# DMP_SEM_MCU.net
KiCad netlist of a schematic drawn in Altium Designer
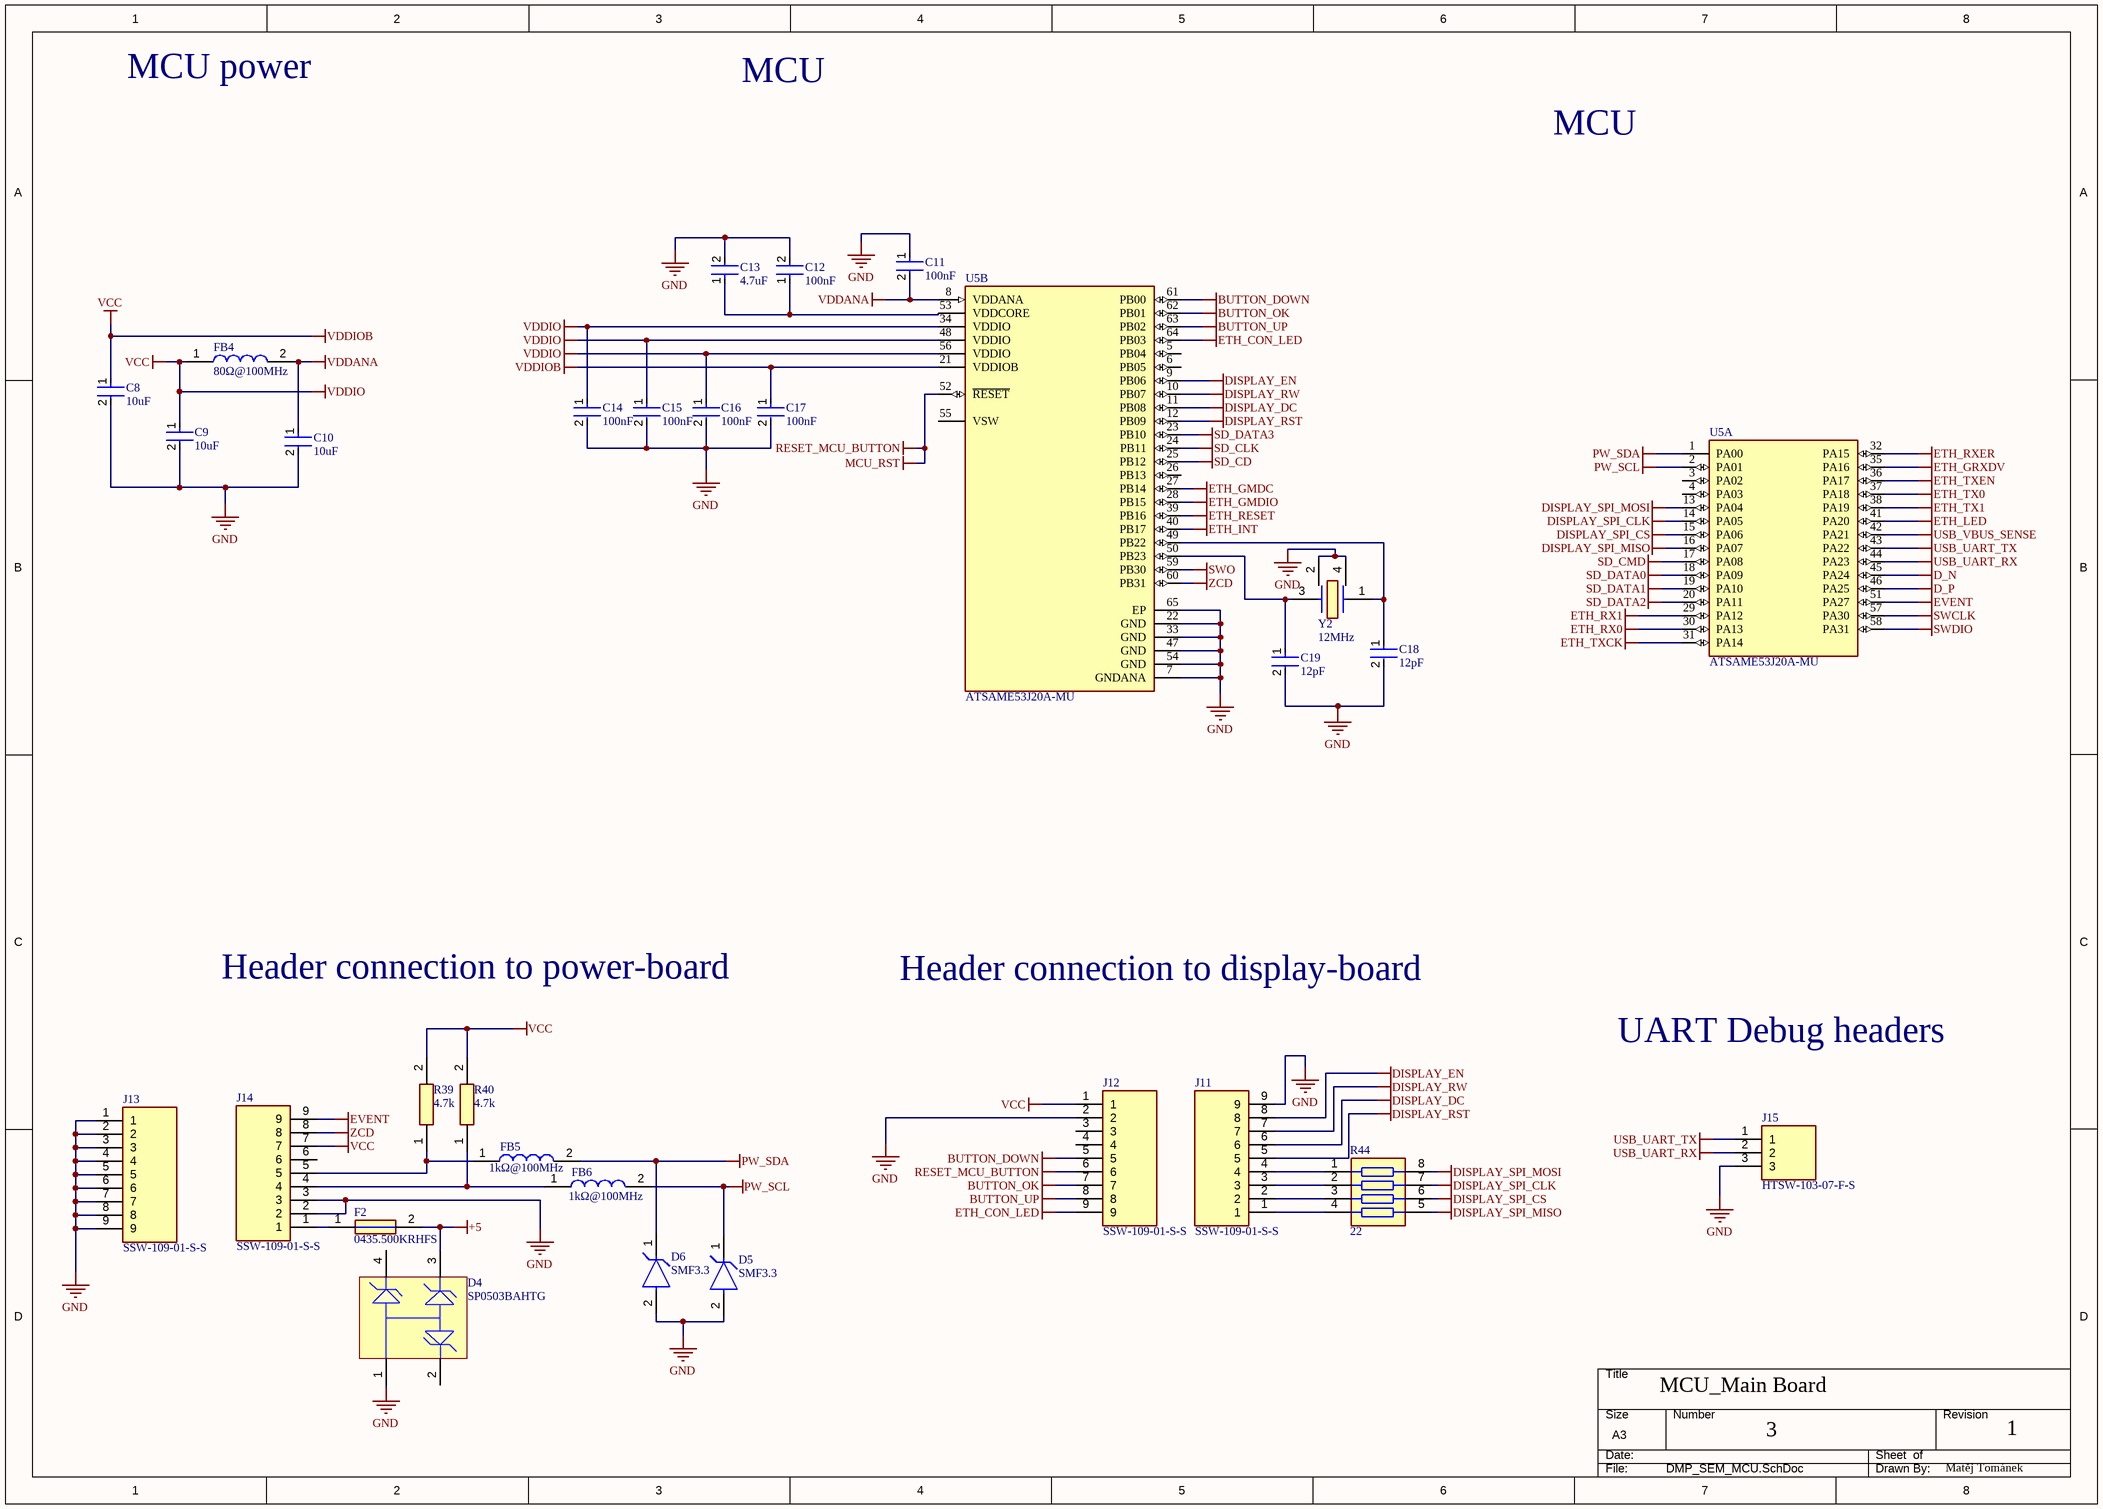
[diagram p0: DMP_SEM_MCU.SchDoc]

(export (version "E")
  (design (tool "Eeschema 10.0.6"))
  (components
    (comp (ref "C8")
      (value "10uF")
      (footprint "CL10A106KO8NQNC")
      (description "Capacitor CL10A106KO8NQNC")
      (libsource (lib "DMP_Schlib_SEM_MAIN_BOARD") (part "CL10A106KO8NQNC"))
    )
    (comp (ref "C9")
      (value "10uF")
      (footprint "CL10A106KO8NQNC")
      (description "Capacitor CL10A106KO8NQNC")
      (libsource (lib "DMP_Schlib_SEM_MAIN_BOARD") (part "CL10A106KO8NQNC"))
    )
    (comp (ref "C10")
      (value "10uF")
      (footprint "CL10A106KO8NQNC")
      (description "Capacitor CL10A106KO8NQNC")
      (libsource (lib "DMP_Schlib_SEM_MAIN_BOARD") (part "CL10A106KO8NQNC"))
    )
    (comp (ref "C11")
      (value "100nF")
      (footprint "CL05B104KO5NNNC")
      (description "Capacitor CL05B104KO5NNNC")
      (libsource (lib "DMP_Schlib_SEM_MAIN_BOARD") (part "CL05B104KO5NNNC"))
    )
    (comp (ref "C12")
      (value "100nF")
      (footprint "CL05B104KO5NNNC")
      (description "Capacitor CL05B104KO5NNNC")
      (libsource (lib "DMP_Schlib_SEM_MAIN_BOARD") (part "CL05B104KO5NNNC"))
    )
    (comp (ref "C13")
      (value "4.7uF")
      (footprint "CL05A475KP5NRNC")
      (description "Capacitor CL05A475KP5NRNC")
      (libsource (lib "DMP_Schlib_SEM_MAIN_BOARD") (part "CL05A475KP5NRNC"))
    )
    (comp (ref "C14")
      (value "100nF")
      (footprint "CL05B104KO5NNNC")
      (description "Capacitor CL05B104KO5NNNC")
      (libsource (lib "DMP_Schlib_SEM_MAIN_BOARD") (part "CL05B104KO5NNNC"))
    )
    (comp (ref "C15")
      (value "100nF")
      (footprint "CL05B104KO5NNNC")
      (description "Capacitor CL05B104KO5NNNC")
      (libsource (lib "DMP_Schlib_SEM_MAIN_BOARD") (part "CL05B104KO5NNNC"))
    )
    (comp (ref "C16")
      (value "100nF")
      (footprint "CL05B104KO5NNNC")
      (description "Capacitor CL05B104KO5NNNC")
      (libsource (lib "DMP_Schlib_SEM_MAIN_BOARD") (part "CL05B104KO5NNNC"))
    )
    (comp (ref "C17")
      (value "100nF")
      (footprint "CL05B104KO5NNNC")
      (description "Capacitor CL05B104KO5NNNC")
      (libsource (lib "DMP_Schlib_SEM_MAIN_BOARD") (part "CL05B104KO5NNNC"))
    )
    (comp (ref "C18")
      (value "12pF")
      (footprint "GRM1555C1H120JA01D")
      (description "Capacitor GRM1555C1H120JA01D")
      (libsource (lib "DMP_Schlib_SEM_MAIN_BOARD") (part "GRM1555C1H120JA01D"))
    )
    (comp (ref "C19")
      (value "12pF")
      (footprint "GRM1555C1H120JA01D")
      (description "Capacitor GRM1555C1H120JA01D")
      (libsource (lib "DMP_Schlib_SEM_MAIN_BOARD") (part "GRM1555C1H120JA01D"))
    )
    (comp (ref "D4")
      (value "SP0503BAHTG")
      (footprint "SP0503BAHTG")
      (description "TVS Diodes SP0503BAHTG")
      (libsource (lib "DMP_Schlib_SEM_MAIN_BOARD") (part "SP0503BAHTG"))
    )
    (comp (ref "D5")
      (value "SMF3.3")
      (footprint "SMF3.3")
      (description "TVS diode SMF3.3")
      (libsource (lib "DMP_Schlib_SEM_MAIN_BOARD") (part "SMF3.3"))
    )
    (comp (ref "D6")
      (value "SMF3.3")
      (footprint "SMF3.3")
      (description "TVS diode SMF3.3")
      (libsource (lib "DMP_Schlib_SEM_MAIN_BOARD") (part "SMF3.3"))
    )
    (comp (ref "F2")
      (value "0435.500KRHFS")
      (footprint "0435.500KRHFS")
      (description "Fuse 0435.500KRHFS")
      (libsource (lib "DMP_Schlib_SEM_MAIN_BOARD") (part "0435.500KRHFS"))
    )
    (comp (ref "FB4")
      (value "80Ω@100MHz")
      (footprint "BLM15PD800SN1D")
      (description "Chip Ferrite Bead BLM15PD800SN1D")
      (libsource (lib "DMP_Schlib_SEM_MAIN_BOARD") (part "BLM15PD800SN1D"))
    )
    (comp (ref "FB5")
      (value "1kΩ@100MHz")
      (footprint "BLM15BD102SN1D")
      (description "Chip Ferrite Bead BLM15BD102SN1D")
      (libsource (lib "DMP_Schlib_SEM_MAIN_BOARD") (part "BLM15BD102SN1D"))
    )
    (comp (ref "FB6")
      (value "1kΩ@100MHz")
      (footprint "BLM15BD102SN1D")
      (description "Chip Ferrite Bead BLM15BD102SN1D")
      (libsource (lib "DMP_Schlib_SEM_MAIN_BOARD") (part "BLM15BD102SN1D"))
    )
    (comp (ref "J11")
      (value "SSW-109-01-S-S")
      (footprint "SSW-109-01-S-S")
      (description "Connector SSW-109-01-S-S")
      (libsource (lib "DMP_Schlib_SEM_MAIN_BOARD") (part "SSW-109-01-S-S"))
    )
    (comp (ref "J12")
      (value "SSW-109-01-S-S")
      (footprint "SSW-109-01-S-S")
      (description "Connector SSW-109-01-S-S")
      (libsource (lib "") (part "SSW-109-01-S-S_1"))
    )
    (comp (ref "J13")
      (value "SSW-109-01-S-S")
      (footprint "SSW-109-01-S-S")
      (description "Connector SSW-109-01-S-S")
      (libsource (lib "") (part "SSW-109-01-S-S_1"))
    )
    (comp (ref "J14")
      (value "SSW-109-01-S-S")
      (footprint "SSW-109-01-S-S")
      (description "Connector SSW-109-01-S-S")
      (libsource (lib "DMP_Schlib_SEM_MAIN_BOARD") (part "SSW-109-01-S-S"))
    )
    (comp (ref "J15")
      (value "HTSW-103-07-F-S")
      (footprint "HTSW-103-07-F-S")
      (description "Headers HTSW-103-07-F-S")
      (libsource (lib "DMP_Schlib_SEM_MAIN_BOARD") (part "HTSW-103-07-F-S"))
    )
    (comp (ref "R39")
      (value "4.7k")
      (footprint "ERJ-3EKF4701V")
      (description "Resistor ERJ-3EKF4701V")
      (libsource (lib "DMP_Schlib_SEM_MAIN_BOARD") (part "ERJ-3EKF4701V"))
    )
    (comp (ref "R40")
      (value "4.7k")
      (footprint "ERJ-3EKF4701V")
      (description "Resistor ERJ-3EKF4701V")
      (libsource (lib "DMP_Schlib_SEM_MAIN_BOARD") (part "ERJ-3EKF4701V"))
    )
    (comp (ref "R44")
      (value "22")
      (footprint "CAY10-220J4LF")
      (description "Resistor array CAY10-220J4LF")
      (libsource (lib "DMP_Schlib_SEM_MAIN_BOARD") (part "CAY10-220J4LF"))
    )
    (comp (ref "U5")
      (value "ATSAME53J20A-MU")
      (footprint "FP-PA-IPC_A")
      (description "IC MCU 32BIT 1MB FLASH 64VQFN")
      (libsource (lib "Altium Content Vault") (part "236593db3e601640e0235ea4da59ade"))
    )
    (comp (ref "Y2")
      (value "12MHz")
      (footprint "ABM8W-12.0000MHZ-6-B1U-T3")
      (description "Crystal ABM8W-12.0000MHZ-6-B1U-T3")
      (libsource (lib "DMP_Schlib_SEM_MAIN_BOARD") (part "ABM8W-12.0000MHZ-6-B1U-T3"))
    )
  )
  (nets
    (net (code "1") (name "+5") (class "Default")
      (node (ref "D4") (pin "3") (pinfunction "3_3") (pintype "passive"))
      (node (ref "F2") (pin "2") (pinfunction "2_2") (pintype "passive"))
    )
    (net (code "2") (name "BUTTON_DOWN") (class "Default")
      (node (ref "J12") (pin "5") (pinfunction "5_5") (pintype "passive"))
      (node (ref "U5") (pin "61") (pinfunction "PB00_61") (pintype "bidirectional"))
    )
    (net (code "3") (name "BUTTON_OK") (class "Default")
      (node (ref "J12") (pin "7") (pinfunction "7_7") (pintype "passive"))
      (node (ref "U5") (pin "62") (pinfunction "PB01_62") (pintype "bidirectional"))
    )
    (net (code "4") (name "BUTTON_UP") (class "Default")
      (node (ref "J12") (pin "8") (pinfunction "8_8") (pintype "passive"))
      (node (ref "U5") (pin "63") (pinfunction "PB02_63") (pintype "bidirectional"))
    )
    (net (code "5") (name "DISPLAY_DC") (class "Default")
      (node (ref "J11") (pin "6") (pinfunction "6_6") (pintype "passive"))
      (node (ref "U5") (pin "11") (pinfunction "PB08_11") (pintype "bidirectional"))
    )
    (net (code "6") (name "DISPLAY_EN") (class "Default")
      (node (ref "J11") (pin "8") (pinfunction "8_8") (pintype "passive"))
      (node (ref "U5") (pin "9") (pinfunction "PB06_9") (pintype "bidirectional"))
    )
    (net (code "7") (name "DISPLAY_RST") (class "Default")
      (node (ref "J11") (pin "5") (pinfunction "5_5") (pintype "passive"))
      (node (ref "U5") (pin "12") (pinfunction "PB09_12") (pintype "bidirectional"))
    )
    (net (code "8") (name "DISPLAY_RW") (class "Default")
      (node (ref "J11") (pin "7") (pinfunction "7_7") (pintype "passive"))
      (node (ref "U5") (pin "10") (pinfunction "PB07_10") (pintype "bidirectional"))
    )
    (net (code "9") (name "DISPLAY_SPI_CLK") (class "Default")
      (node (ref "R44") (pin "7") (pintype "passive"))
      (node (ref "U5") (pin "14") (pinfunction "PA05_14") (pintype "bidirectional"))
    )
    (net (code "10") (name "DISPLAY_SPI_CS") (class "Default")
      (node (ref "R44") (pin "6") (pintype "passive"))
      (node (ref "U5") (pin "15") (pinfunction "PA06_15") (pintype "bidirectional"))
    )
    (net (code "11") (name "DISPLAY_SPI_MISO") (class "Default")
      (node (ref "R44") (pin "5") (pintype "passive"))
      (node (ref "U5") (pin "16") (pinfunction "PA07_16") (pintype "bidirectional"))
    )
    (net (code "12") (name "DISPLAY_SPI_MOSI") (class "Default")
      (node (ref "R44") (pin "8") (pintype "passive"))
      (node (ref "U5") (pin "13") (pinfunction "PA04_13") (pintype "bidirectional"))
    )
    (net (code "13") (name "D_N") (class "Default")
      (node (ref "U5") (pin "45") (pinfunction "PA24_45") (pintype "bidirectional"))
    )
    (net (code "14") (name "D_P") (class "Default")
      (node (ref "U5") (pin "46") (pinfunction "PA25_46") (pintype "bidirectional"))
    )
    (net (code "15") (name "ETH_CON_LED") (class "Default")
      (node (ref "J12") (pin "9") (pinfunction "9_9") (pintype "passive"))
      (node (ref "U5") (pin "64") (pinfunction "PB03_64") (pintype "bidirectional"))
    )
    (net (code "16") (name "ETH_GMDC") (class "Default")
      (node (ref "U5") (pin "27") (pinfunction "PB14_27") (pintype "bidirectional"))
    )
    (net (code "17") (name "ETH_GMDIO") (class "Default")
      (node (ref "U5") (pin "28") (pinfunction "PB15_28") (pintype "bidirectional"))
    )
    (net (code "18") (name "ETH_GRXDV") (class "Default")
      (node (ref "U5") (pin "35") (pinfunction "PA16_35") (pintype "bidirectional"))
    )
    (net (code "19") (name "ETH_INT") (class "Default")
      (node (ref "U5") (pin "40") (pinfunction "PB17_40") (pintype "bidirectional"))
    )
    (net (code "20") (name "ETH_LED") (class "Default")
      (node (ref "U5") (pin "41") (pinfunction "PA20_41") (pintype "bidirectional"))
    )
    (net (code "21") (name "ETH_RESET") (class "Default")
      (node (ref "U5") (pin "39") (pinfunction "PB16_39") (pintype "bidirectional"))
    )
    (net (code "22") (name "ETH_RX0") (class "Default")
      (node (ref "U5") (pin "30") (pinfunction "PA13_30") (pintype "bidirectional"))
    )
    (net (code "23") (name "ETH_RX1") (class "Default")
      (node (ref "U5") (pin "29") (pinfunction "PA12_29") (pintype "bidirectional"))
    )
    (net (code "24") (name "ETH_RXER") (class "Default")
      (node (ref "U5") (pin "32") (pinfunction "PA15_32") (pintype "bidirectional"))
    )
    (net (code "25") (name "ETH_TX0") (class "Default")
      (node (ref "U5") (pin "37") (pinfunction "PA18_37") (pintype "bidirectional"))
    )
    (net (code "26") (name "ETH_TX1") (class "Default")
      (node (ref "U5") (pin "38") (pinfunction "PA19_38") (pintype "bidirectional"))
    )
    (net (code "27") (name "ETH_TXCK") (class "Default")
      (node (ref "U5") (pin "31") (pinfunction "PA14_31") (pintype "bidirectional"))
    )
    (net (code "28") (name "ETH_TXEN") (class "Default")
      (node (ref "U5") (pin "36") (pinfunction "PA17_36") (pintype "bidirectional"))
    )
    (net (code "29") (name "EVENT") (class "Default")
      (node (ref "J14") (pin "9") (pinfunction "9_9") (pintype "passive"))
      (node (ref "U5") (pin "51") (pinfunction "PA27_51") (pintype "bidirectional"))
    )
    (net (code "30") (name "GND") (class "Default")
      (node (ref "C10") (pin "2") (pinfunction "2_2") (pintype "passive"))
      (node (ref "C11") (pin "1") (pinfunction "1_1") (pintype "passive"))
      (node (ref "C12") (pin "2") (pinfunction "2_2") (pintype "passive"))
      (node (ref "C13") (pin "2") (pinfunction "2_2") (pintype "passive"))
      (node (ref "C14") (pin "2") (pinfunction "2_2") (pintype "passive"))
      (node (ref "C15") (pin "2") (pinfunction "2_2") (pintype "passive"))
      (node (ref "C16") (pin "2") (pinfunction "2_2") (pintype "passive"))
      (node (ref "C17") (pin "2") (pinfunction "2_2") (pintype "passive"))
      (node (ref "C18") (pin "2") (pinfunction "2_2") (pintype "passive"))
      (node (ref "C19") (pin "2") (pinfunction "2_2") (pintype "passive"))
      (node (ref "C8") (pin "2") (pinfunction "2_2") (pintype "passive"))
      (node (ref "C9") (pin "2") (pinfunction "2_2") (pintype "passive"))
      (node (ref "D4") (pin "1") (pinfunction "1_1") (pintype "passive"))
      (node (ref "D5") (pin "2") (pinfunction "A_2") (pintype "passive"))
      (node (ref "D6") (pin "2") (pinfunction "A_2") (pintype "passive"))
      (node (ref "J11") (pin "9") (pinfunction "9_9") (pintype "passive"))
      (node (ref "J12") (pin "2") (pinfunction "2_2") (pintype "passive"))
      (node (ref "J13") (pin "1") (pinfunction "1_1") (pintype "passive"))
      (node (ref "J13") (pin "2") (pinfunction "2_2") (pintype "passive"))
      (node (ref "J13") (pin "3") (pinfunction "3_3") (pintype "passive"))
      (node (ref "J13") (pin "4") (pinfunction "4_4") (pintype "passive"))
      (node (ref "J13") (pin "5") (pinfunction "5_5") (pintype "passive"))
      (node (ref "J13") (pin "6") (pinfunction "6_6") (pintype "passive"))
      (node (ref "J13") (pin "7") (pinfunction "7_7") (pintype "passive"))
      (node (ref "J13") (pin "8") (pinfunction "8_8") (pintype "passive"))
      (node (ref "J13") (pin "9") (pinfunction "9_9") (pintype "passive"))
      (node (ref "J14") (pin "2") (pinfunction "2_2") (pintype "passive"))
      (node (ref "J14") (pin "3") (pinfunction "3_3") (pintype "passive"))
      (node (ref "J15") (pin "3") (pinfunction "3_3") (pintype "passive"))
      (node (ref "U5") (pin "22") (pinfunction "GND_22") (pintype "power_in"))
      (node (ref "U5") (pin "33") (pinfunction "GND_33") (pintype "power_in"))
      (node (ref "U5") (pin "47") (pinfunction "GND_47") (pintype "power_in"))
      (node (ref "U5") (pin "54") (pinfunction "GND_54") (pintype "power_in"))
      (node (ref "U5") (pin "65") (pinfunction "EP_65") (pintype "power_in"))
      (node (ref "U5") (pin "7") (pinfunction "GNDANA_7") (pintype "power_in"))
      (node (ref "Y2") (pin "2") (pintype "passive"))
      (node (ref "Y2") (pin "4") (pintype "passive"))
    )
    (net (code "31") (name "MCU_RST") (class "Default")
      (node (ref "J12") (pin "6") (pinfunction "6_6") (pintype "passive"))
      (node (ref "U5") (pin "52") (pinfunction "~{RESET}_52") (pintype "bidirectional"))
    )
    (net (code "32") (name "Net-(F2-Pad1)") (class "Default")
      (node (ref "F2") (pin "1") (pinfunction "1_1") (pintype "passive"))
      (node (ref "J14") (pin "1") (pinfunction "1_1") (pintype "passive"))
    )
    (net (code "33") (name "Net-(FB5-Pad1)") (class "Default")
      (node (ref "FB5") (pin "1") (pinfunction "1_1") (pintype "passive"))
      (node (ref "J14") (pin "5") (pinfunction "5_5") (pintype "passive"))
      (node (ref "R39") (pin "1") (pinfunction "1_1") (pintype "passive"))
    )
    (net (code "34") (name "Net-(FB6-Pad1)") (class "Default")
      (node (ref "FB6") (pin "1") (pinfunction "1_1") (pintype "passive"))
      (node (ref "J14") (pin "4") (pinfunction "4_4") (pintype "passive"))
      (node (ref "R40") (pin "1") (pinfunction "1_1") (pintype "passive"))
    )
    (net (code "35") (name "Net-(J11-Pad1)") (class "Default")
      (node (ref "J11") (pin "1") (pinfunction "1_1") (pintype "passive"))
      (node (ref "R44") (pin "4") (pintype "passive"))
    )
    (net (code "36") (name "Net-(J11-Pad2)") (class "Default")
      (node (ref "J11") (pin "2") (pinfunction "2_2") (pintype "passive"))
      (node (ref "R44") (pin "3") (pintype "passive"))
    )
    (net (code "37") (name "Net-(J11-Pad3)") (class "Default")
      (node (ref "J11") (pin "3") (pinfunction "3_3") (pintype "passive"))
      (node (ref "R44") (pin "2") (pintype "passive"))
    )
    (net (code "38") (name "Net-(J11-Pad4)") (class "Default")
      (node (ref "J11") (pin "4") (pinfunction "4_4") (pintype "passive"))
      (node (ref "R44") (pin "1") (pintype "passive"))
    )
    (net (code "39") (name "Net-(U5B-PB22)") (class "Default")
      (node (ref "C18") (pin "1") (pinfunction "1_1") (pintype "passive"))
      (node (ref "U5") (pin "49") (pinfunction "PB22_49") (pintype "bidirectional"))
      (node (ref "Y2") (pin "1") (pintype "passive"))
    )
    (net (code "40") (name "Net-(U5B-PB23)") (class "Default")
      (node (ref "C19") (pin "1") (pinfunction "1_1") (pintype "passive"))
      (node (ref "U5") (pin "50") (pinfunction "PB23_50") (pintype "bidirectional"))
      (node (ref "Y2") (pin "3") (pintype "passive"))
    )
    (net (code "41") (name "Net-(U5B-VDDCORE)") (class "Default")
      (node (ref "C12") (pin "1") (pinfunction "1_1") (pintype "passive"))
      (node (ref "C13") (pin "1") (pinfunction "1_1") (pintype "passive"))
      (node (ref "U5") (pin "53") (pinfunction "VDDCORE_53") (pintype "power_in"))
    )
    (net (code "42") (name "PW_SCL") (class "Default")
      (node (ref "D5") (pin "1") (pinfunction "C_1") (pintype "passive"))
      (node (ref "FB6") (pin "2") (pinfunction "2_2") (pintype "passive"))
      (node (ref "U5") (pin "2") (pinfunction "PA01_2") (pintype "bidirectional"))
    )
    (net (code "43") (name "PW_SDA") (class "Default")
      (node (ref "D6") (pin "1") (pinfunction "C_1") (pintype "passive"))
      (node (ref "FB5") (pin "2") (pinfunction "2_2") (pintype "passive"))
      (node (ref "U5") (pin "1") (pinfunction "PA00_1") (pintype "power_in"))
    )
    (net (code "44") (name "SD_CD") (class "Default")
      (node (ref "U5") (pin "25") (pinfunction "PB12_25") (pintype "bidirectional"))
    )
    (net (code "45") (name "SD_CLK") (class "Default")
      (node (ref "U5") (pin "24") (pinfunction "PB11_24") (pintype "bidirectional"))
    )
    (net (code "46") (name "SD_CMD") (class "Default")
      (node (ref "U5") (pin "17") (pinfunction "PA08_17") (pintype "bidirectional"))
    )
    (net (code "47") (name "SD_DATA0") (class "Default")
      (node (ref "U5") (pin "18") (pinfunction "PA09_18") (pintype "bidirectional"))
    )
    (net (code "48") (name "SD_DATA1") (class "Default")
      (node (ref "U5") (pin "19") (pinfunction "PA10_19") (pintype "bidirectional"))
    )
    (net (code "49") (name "SD_DATA2") (class "Default")
      (node (ref "U5") (pin "20") (pinfunction "PA11_20") (pintype "bidirectional"))
    )
    (net (code "50") (name "SD_DATA3") (class "Default")
      (node (ref "U5") (pin "23") (pinfunction "PB10_23") (pintype "bidirectional"))
    )
    (net (code "51") (name "SWCLK") (class "Default")
      (node (ref "U5") (pin "57") (pinfunction "PA30_57") (pintype "bidirectional"))
    )
    (net (code "52") (name "SWDIO") (class "Default")
      (node (ref "U5") (pin "58") (pinfunction "PA31_58") (pintype "bidirectional"))
    )
    (net (code "53") (name "SWO") (class "Default")
      (node (ref "U5") (pin "59") (pinfunction "PB30_59") (pintype "bidirectional"))
    )
    (net (code "54") (name "USB_UART_RX") (class "Default")
      (node (ref "J15") (pin "2") (pinfunction "2_2") (pintype "passive"))
      (node (ref "U5") (pin "44") (pinfunction "PA23_44") (pintype "bidirectional"))
    )
    (net (code "55") (name "USB_UART_TX") (class "Default")
      (node (ref "J15") (pin "1") (pinfunction "1_1") (pintype "passive"))
      (node (ref "U5") (pin "43") (pinfunction "PA22_43") (pintype "bidirectional"))
    )
    (net (code "56") (name "USB_VBUS_SENSE") (class "Default")
      (node (ref "U5") (pin "42") (pinfunction "PA21_42") (pintype "bidirectional"))
    )
    (net (code "57") (name "VCC") (class "Default")
      (node (ref "C14") (pin "1") (pinfunction "1_1") (pintype "passive"))
      (node (ref "C15") (pin "1") (pinfunction "1_1") (pintype "passive"))
      (node (ref "C16") (pin "1") (pinfunction "1_1") (pintype "passive"))
      (node (ref "C17") (pin "1") (pinfunction "1_1") (pintype "passive"))
      (node (ref "C8") (pin "1") (pinfunction "1_1") (pintype "passive"))
      (node (ref "C9") (pin "1") (pinfunction "1_1") (pintype "passive"))
      (node (ref "FB4") (pin "1") (pinfunction "1_1") (pintype "passive"))
      (node (ref "J12") (pin "1") (pinfunction "1_1") (pintype "passive"))
      (node (ref "J14") (pin "7") (pinfunction "7_7") (pintype "passive"))
      (node (ref "R39") (pin "2") (pinfunction "2_2") (pintype "passive"))
      (node (ref "R40") (pin "2") (pinfunction "2_2") (pintype "passive"))
      (node (ref "U5") (pin "21") (pinfunction "VDDIOB_21") (pintype "power_in"))
      (node (ref "U5") (pin "34") (pinfunction "VDDIO_34") (pintype "power_in"))
      (node (ref "U5") (pin "48") (pinfunction "VDDIO_48") (pintype "power_in"))
      (node (ref "U5") (pin "56") (pinfunction "VDDIO_56") (pintype "power_in"))
    )
    (net (code "58") (name "VDDANA") (class "Default")
      (node (ref "C10") (pin "1") (pinfunction "1_1") (pintype "passive"))
      (node (ref "C11") (pin "2") (pinfunction "2_2") (pintype "passive"))
      (node (ref "FB4") (pin "2") (pinfunction "2_2") (pintype "passive"))
      (node (ref "U5") (pin "8") (pinfunction "VDDANA_8") (pintype "input"))
    )
    (net (code "59") (name "ZCD") (class "Default")
      (node (ref "J14") (pin "8") (pinfunction "8_8") (pintype "passive"))
      (node (ref "U5") (pin "60") (pinfunction "PB31_60") (pintype "bidirectional"))
    )
    (net (code "60") (name "unconnected-(D4-Pad2)") (class "Default")
      (node (ref "D4") (pin "2") (pinfunction "2_2") (pintype "passive"))
    )
    (net (code "61") (name "unconnected-(D4-Pad4)") (class "Default")
      (node (ref "D4") (pin "4") (pinfunction "4_4") (pintype "passive"))
    )
    (net (code "62") (name "unconnected-(J12-Pad3)") (class "Default")
      (node (ref "J12") (pin "3") (pinfunction "3_3") (pintype "passive"))
    )
    (net (code "63") (name "unconnected-(J12-Pad4)") (class "Default")
      (node (ref "J12") (pin "4") (pinfunction "4_4") (pintype "passive"))
    )
    (net (code "64") (name "unconnected-(J14-Pad6)") (class "Default")
      (node (ref "J14") (pin "6") (pinfunction "6_6") (pintype "passive"))
    )
    (net (code "65") (name "unconnected-(U5A-PA02-Pad3)") (class "Default")
      (node (ref "U5") (pin "3") (pinfunction "PA02_3") (pintype "bidirectional"))
    )
    (net (code "66") (name "unconnected-(U5A-PA03-Pad4)") (class "Default")
      (node (ref "U5") (pin "4") (pinfunction "PA03_4") (pintype "bidirectional"))
    )
    (net (code "67") (name "unconnected-(U5B-PB04-Pad5)") (class "Default")
      (node (ref "U5") (pin "5") (pinfunction "PB04_5") (pintype "bidirectional"))
    )
    (net (code "68") (name "unconnected-(U5B-PB05-Pad6)") (class "Default")
      (node (ref "U5") (pin "6") (pinfunction "PB05_6") (pintype "bidirectional"))
    )
    (net (code "69") (name "unconnected-(U5B-PB13-Pad26)") (class "Default")
      (node (ref "U5") (pin "26") (pinfunction "PB13_26") (pintype "bidirectional"))
    )
    (net (code "70") (name "unconnected-(U5B-VSW-Pad55)") (class "Default")
      (node (ref "U5") (pin "55") (pinfunction "VSW_55") (pintype "power_in"))
    )
  )
)
